# TPS6513x.net
KiCad netlist of a schematic drawn in Altium Designer
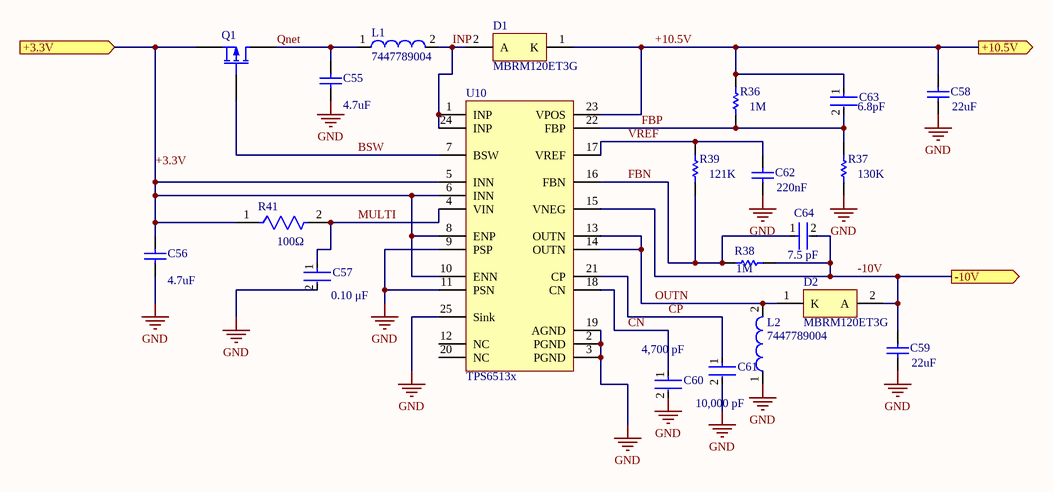
[diagram p0: TPS6513x.SchDoc]

(export (version "E")
  (design (tool "Eeschema 10.0.6"))
  (components
    (comp (ref "C55")
      (value "4.7uF")
      (footprint "Yemet_0603")
      (description "Capacitor")
      (fields (field (name "Comment") "Comment") (field (name "PUBLISHER") "Altium Limited"))
      (libsource (lib "Miscellaneous Devices") (part "Cap"))
    )
    (comp (ref "C56")
      (value "4.7uF")
      (footprint "Yemet_0603")
      (description "Capacitor")
      (fields (field (name "Comment") "Comment") (field (name "PUBLISHER") "Altium Limited"))
      (libsource (lib "Miscellaneous Devices") (part "Cap"))
    )
    (comp (ref "C57")
      (value "0.10 μF")
      (footprint "Yemet_0603")
      (description "C0402 0.10 μF X5R 10.00% 10 V")
      (fields
        (field (name "MANUFACTURER PART NUMBER") "C0402C104K8PAC")
        (field (name "MANUFACTURER") "Kemet")
      )
      (libsource (lib "Miscellaneous Devices") (part "b4654b650e69147ec39a6b967a45e02"))
    )
    (comp (ref "C58")
      (value "22uF")
      (footprint "GRM32ER71E226KE15K")
      (description "Capacitor")
      (fields (field (name "Comment") "Comment") (field (name "PUBLISHER") "Altium Limited"))
      (libsource (lib "Miscellaneous Devices") (part "Cap"))
    )
    (comp (ref "C59")
      (value "22uF")
      (footprint "GRM32ER71E226KE15K")
      (description "Capacitor")
      (fields (field (name "Comment") "Comment") (field (name "PUBLISHER") "Altium Limited"))
      (libsource (lib "Miscellaneous Devices") (part "Cap"))
    )
    (comp (ref "C60")
      (value "C1206C472J5GAC")
      (footprint "Yemet_0603")
      (description "C1206 4,700 pF C0G 5.00% 50 V")
      (fields
        (field (name "OCTOPART") "https://octopart.com/c1206c472j5gac-kemet-1350327")
        (field (name "MANUFACTURER") "KEMET")
        (field (name "CAPACITANCE") "4,700 pF")
      )
      (libsource (lib "Miscellaneous Devices") (part "b4654b650e69147ec39a6b967a45e02"))
    )
    (comp (ref "C61")
      (value "10,000 pF")
      (footprint "Yemet_0603")
      (description "C0402 10,000 pF X7R 5.00% 16 V")
      (fields (field (name "MANUFACTURER PART NUMBER") "C0402C103J4RAC") (field (name "TOLERANCE") "0.05"))
      (libsource (lib "Miscellaneous Devices") (part "b4654b650e69147ec39a6b967a45e02"))
    )
    (comp (ref "C62")
      (value "220nF")
      (footprint "Yemet_0603")
      (description "Capacitor")
      (fields (field (name "Comment") "Comment") (field (name "PUBLISHER") "Altium Limited"))
      (libsource (lib "Miscellaneous Devices") (part "Cap"))
    )
    (comp (ref "C63")
      (value "CGA1A2C0G1E6R8D030BA")
      (footprint "885012007027")
      (description "Cap Ceramic 6.8pF 25V C0G 0.5pF Pad SMD 0201 125°C Automotive T/R")
      (fields (field (name "CAPACITANCE") "6.8pF"))
      (libsource (lib "Miscellaneous Devices") (part "b4654b650e69147ec39a6b967a45e02"))
    )
    (comp (ref "C64")
      (value "7.5 pF")
      (footprint "FP-C0805C-DN-MFG")
      (description "CAP CER 7.5PF 50V NP0 0805")
      (fields (field (name "MANUFACTURER") "KEMET") (field (name "TOLERANCE") "0.5 pF"))
      (libsource (lib "Altium Content Vault") (part "b4654b650e69147ec39a6b967a45e02"))
    )
    (comp (ref "D1")
      (value "MBRM120ET3G")
      (footprint "ONSC-POWERMITE-2-457-04_D_V")
      (description "Schottky Power Rectifier, 2-Pin Powermite, Pb-Free, Tape and Reel")
      (fields (field (name "MANUFACTURER") "On Semiconductor"))
      (libsource (lib "") (part "ONSC-D-K1A2-2_A_1"))
    )
    (comp (ref "D2")
      (value "MBRM120ET3G")
      (footprint "ONSC-POWERMITE-2-457-04_D_V")
      (description "Schottky Power Rectifier, 2-Pin Powermite, Pb-Free, Tape and Reel")
      (fields (field (name "MANUFACTURER") "On Semiconductor"))
      (libsource (lib "Altium Content Vault") (part "ONSC-D-K1A2-2_A"))
    )
    (comp (ref "L1")
      (value "7447789004")
      (footprint "WE-PD-S-PB")
      (description "SMD-Shielded Power Inductor WE-PD, L=4.70 µH")
      (fields (field (name "MANUFACTURER") "Wuerth Elektronik"))
      (libsource (lib "Altium Content Vault") (part "PAS-IND-INDUCTOR-2"))
    )
    (comp (ref "L2")
      (value "7447789004")
      (footprint "WE-PD-S-PB")
      (description "SMD-Shielded Power Inductor WE-PD, L=4.70 µH")
      (fields (field (name "MANUFACTURER") "Wuerth Elektronik"))
      (libsource (lib "Altium Content Vault") (part "PAS-IND-INDUCTOR-2"))
    )
    (comp (ref "Q1")
      (value "Comment")
      (footprint "PCBComponent_1")
      (description "P-Channel MOSFET")
      (fields (field (name "PUBLISHER") "Altium Limited"))
      (libsource (lib "Miscellaneous Devices") (part "MOSFET-P"))
    )
    (comp (ref "R36")
      (value "1M")
      (footprint "0603res_Yageo")
      (description "Resistor")
      (fields (field (name "Comment") "ESR01MZPF1004") (field (name "PUBLISHER") "Altium Limited"))
      (libsource (lib "Miscellaneous Devices") (part "Res1"))
    )
    (comp (ref "R37")
      (value "130K")
      (footprint "SFR03EZPF1303")
      (description "Resistor")
      (fields (field (name "Comment") "SFR03EZPF1303") (field (name "PUBLISHER") "Altium Limited"))
      (libsource (lib "Miscellaneous Devices") (part "Res1"))
    )
    (comp (ref "R38")
      (value "1M")
      (footprint "0603res_Yageo")
      (description "Resistor")
      (fields (field (name "Comment") "Comment") (field (name "PUBLISHER") "Altium Limited"))
      (libsource (lib "Miscellaneous Devices") (part "Res1"))
    )
    (comp (ref "R39")
      (value "121K")
      (footprint "0603res_Yageo")
      (description "Resistor")
      (fields (field (name "Comment") "Comment") (field (name "PUBLISHER") "Altium Limited"))
      (libsource (lib "Miscellaneous Devices") (part "Res1"))
    )
    (comp (ref "R41")
      (value "AC0603FR-10100RL")
      (footprint "0603res_Yageo")
      (description "RES 100Ω 1.00% 0.1W 0603")
      (fields (field (name "TOLERANCE") "1%") (field (name "RESISTANCE") "100Ω"))
      (libsource (lib "Miscellaneous Devices") (part "1029c3af85768c4190bb7ad29bc67b5"))
    )
    (comp (ref "U10")
      (value "TPS6513x")
      (footprint "TPS6513final")
      (fields (field (name "PARTNUMBER") "TPS65130RGER") (field (name "MANUFACTURER") "Texas Instruments"))
      (libsource (lib "Buck_and_Inverter") (part "TI-TPS65130RGE24-2450X2450TP"))
    )
  )
  (nets
    (net (code "1") (name "/+3.3V") (class "Default")
      (node (ref "C56") (pin "1") (pinfunction "1_1") (pintype "passive"))
      (node (ref "Q1") (pin "3") (pinfunction "S_3") (pintype "passive"))
      (node (ref "R41") (pin "1") (pinfunction "1_1") (pintype "passive"))
      (node (ref "U10") (pin "10") (pinfunction "ENN_10") (pintype "passive"))
      (node (ref "U10") (pin "5") (pinfunction "INN_5") (pintype "passive"))
      (node (ref "U10") (pin "6") (pinfunction "INN_6") (pintype "passive"))
      (node (ref "U10") (pin "8") (pinfunction "ENP_8") (pintype "passive"))
    )
    (net (code "2") (name "/+10.5V") (class "Default")
      (node (ref "C58") (pin "2") (pinfunction "2_2") (pintype "passive"))
      (node (ref "C63") (pin "1") (pinfunction "1_1") (pintype "passive"))
      (node (ref "D1") (pin "1") (pinfunction "K_1") (pintype "passive"))
      (node (ref "R36") (pin "2") (pinfunction "2_2") (pintype "passive"))
      (node (ref "U10") (pin "23") (pinfunction "VPOS_23") (pintype "passive"))
    )
    (net (code "3") (name "/-10V") (class "Default")
      (node (ref "C59") (pin "2") (pinfunction "2_2") (pintype "passive"))
      (node (ref "C64") (pin "2") (pinfunction "2_2") (pintype "passive"))
      (node (ref "D2") (pin "2") (pinfunction "A_2") (pintype "passive"))
      (node (ref "R38") (pin "1") (pinfunction "1_1") (pintype "passive"))
      (node (ref "U10") (pin "15") (pinfunction "VNEG_15") (pintype "passive"))
    )
    (net (code "4") (name "/BSW") (class "Default")
      (node (ref "Q1") (pin "2") (pinfunction "G_2") (pintype "passive"))
      (node (ref "U10") (pin "7") (pinfunction "BSW_7") (pintype "passive"))
    )
    (net (code "5") (name "/CN") (class "Default")
      (node (ref "C60") (pin "1") (pinfunction "1_1") (pintype "passive"))
      (node (ref "U10") (pin "18") (pinfunction "CN_18") (pintype "passive"))
    )
    (net (code "6") (name "/CP") (class "Default")
      (node (ref "C61") (pin "1") (pinfunction "1_1") (pintype "passive"))
      (node (ref "U10") (pin "21") (pinfunction "CP_21") (pintype "passive"))
    )
    (net (code "7") (name "/FBN") (class "Default")
      (node (ref "C64") (pin "1") (pinfunction "1_1") (pintype "passive"))
      (node (ref "R38") (pin "2") (pinfunction "2_2") (pintype "passive"))
      (node (ref "R39") (pin "1") (pinfunction "1_1") (pintype "passive"))
      (node (ref "U10") (pin "16") (pinfunction "FBN_16") (pintype "passive"))
    )
    (net (code "8") (name "/FBP") (class "Default")
      (node (ref "C63") (pin "2") (pinfunction "2_2") (pintype "passive"))
      (node (ref "R36") (pin "1") (pinfunction "1_1") (pintype "passive"))
      (node (ref "R37") (pin "2") (pinfunction "2_2") (pintype "passive"))
      (node (ref "U10") (pin "22") (pinfunction "FBP_22") (pintype "passive"))
    )
    (net (code "9") (name "/INP") (class "Default")
      (node (ref "D1") (pin "2") (pinfunction "A_2") (pintype "passive"))
      (node (ref "L1") (pin "2") (pinfunction "2_2") (pintype "passive"))
      (node (ref "U10") (pin "1") (pinfunction "INP_1") (pintype "passive"))
      (node (ref "U10") (pin "24") (pinfunction "INP_24") (pintype "passive"))
    )
    (net (code "10") (name "/MULTI") (class "Default")
      (node (ref "C57") (pin "1") (pinfunction "1_1") (pintype "passive"))
      (node (ref "R41") (pin "2") (pinfunction "2_2") (pintype "passive"))
      (node (ref "U10") (pin "4") (pinfunction "VIN_4") (pintype "passive"))
    )
    (net (code "11") (name "/OUTN") (class "Default")
      (node (ref "D2") (pin "1") (pinfunction "K_1") (pintype "passive"))
      (node (ref "L2") (pin "2") (pinfunction "2_2") (pintype "passive"))
      (node (ref "U10") (pin "13") (pinfunction "OUTN_13") (pintype "passive"))
      (node (ref "U10") (pin "14") (pinfunction "OUTN_14") (pintype "passive"))
    )
    (net (code "12") (name "/Qnet") (class "Default")
      (node (ref "C55") (pin "1") (pinfunction "1_1") (pintype "passive"))
      (node (ref "L1") (pin "1") (pinfunction "1_1") (pintype "passive"))
      (node (ref "Q1") (pin "1") (pinfunction "D_1") (pintype "passive"))
    )
    (net (code "13") (name "/VREF") (class "Default")
      (node (ref "C62") (pin "2") (pinfunction "2_2") (pintype "passive"))
      (node (ref "R39") (pin "2") (pinfunction "2_2") (pintype "passive"))
      (node (ref "U10") (pin "17") (pinfunction "VREF_17") (pintype "passive"))
    )
    (net (code "14") (name "GND") (class "Default")
      (node (ref "C55") (pin "2") (pinfunction "2_2") (pintype "passive"))
      (node (ref "C56") (pin "2") (pinfunction "2_2") (pintype "passive"))
      (node (ref "C57") (pin "2") (pinfunction "2_2") (pintype "passive"))
      (node (ref "C58") (pin "1") (pinfunction "1_1") (pintype "passive"))
      (node (ref "C59") (pin "1") (pinfunction "1_1") (pintype "passive"))
      (node (ref "C60") (pin "2") (pinfunction "2_2") (pintype "passive"))
      (node (ref "C61") (pin "2") (pinfunction "2_2") (pintype "passive"))
      (node (ref "C62") (pin "1") (pinfunction "1_1") (pintype "passive"))
      (node (ref "L2") (pin "1") (pinfunction "1_1") (pintype "passive"))
      (node (ref "R37") (pin "1") (pinfunction "1_1") (pintype "passive"))
      (node (ref "U10") (pin "11") (pinfunction "PSN_11") (pintype "passive"))
      (node (ref "U10") (pin "19") (pinfunction "AGND_19") (pintype "passive"))
      (node (ref "U10") (pin "2") (pinfunction "PGND_2") (pintype "passive"))
      (node (ref "U10") (pin "25") (pinfunction "Sink_25") (pintype "passive"))
      (node (ref "U10") (pin "3") (pinfunction "PGND_3") (pintype "passive"))
      (node (ref "U10") (pin "9") (pinfunction "PSP_9") (pintype "passive"))
    )
    (net (code "15") (name "unconnected-(U10-NC-Pad12)") (class "Default")
      (node (ref "U10") (pin "12") (pinfunction "NC_12") (pintype "passive"))
    )
    (net (code "16") (name "unconnected-(U10-NC-Pad20)") (class "Default")
      (node (ref "U10") (pin "20") (pinfunction "NC_20") (pintype "passive"))
    )
  )
)
